# Pressure_Sensor.net
KiCad netlist of a schematic drawn in Altium Designer
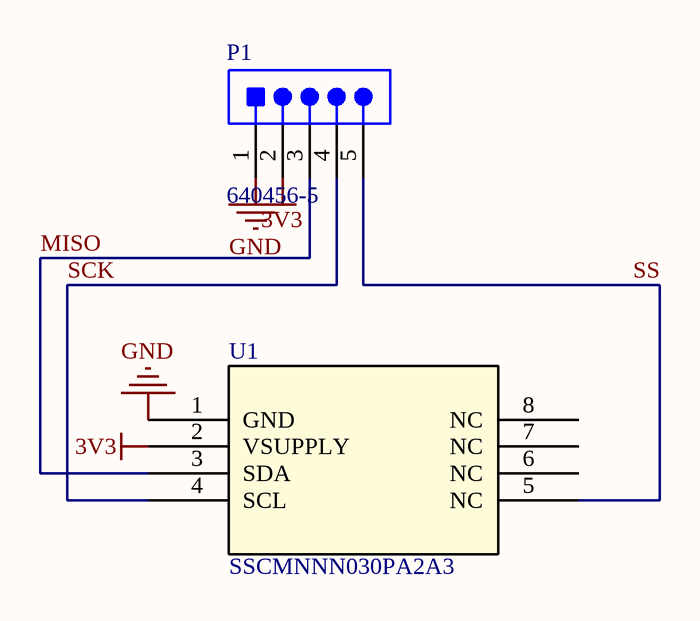
[diagram p0: Pressure Sensor.SchDoc]

(export (version "E")
  (design (tool "Eeschema 10.0.6"))
  (components
    (comp (ref "P1")
      (value "640456-5")
      (footprint "TECO-640456-5")
      (fields (field (name "MANUFACTURER") "TE Connectivity"))
      (libsource (lib "Altium Content Vault") (part "CN-1P-M-R5"))
    )
    (comp (ref "U1")
      (value "SSCMNNN030PA2A3")
      (footprint "SSCMNN_HNW-L")
      (description "No Description Available")
      (fields (field (name "COPYRIGHT") "Copyright (C) 2018 Accelerated Designs. All rights reserved"))
      (libsource (lib "2020-10-01_16-01-06") (part "SSCMNNN030PA2A3"))
    )
  )
  (nets
    (net (code "1") (name "/MISO") (class "Default")
      (node (ref "P1") (pin "3") (pinfunction "TXO_3") (pintype "passive"))
      (node (ref "U1") (pin "3") (pinfunction "SDA_3") (pintype "passive"))
    )
    (net (code "2") (name "/SCK") (class "Default")
      (node (ref "P1") (pin "4") (pinfunction "VCC_4") (pintype "passive"))
      (node (ref "U1") (pin "4") (pinfunction "SCL_4") (pintype "passive"))
    )
    (net (code "3") (name "/SS") (class "Default")
      (node (ref "P1") (pin "5") (pinfunction "CTS_5") (pintype "passive"))
      (node (ref "U1") (pin "5") (pinfunction "NC_5") (pintype "passive"))
    )
    (net (code "4") (name "3V3") (class "Default")
      (node (ref "P1") (pin "2") (pinfunction "RXI_2") (pintype "passive"))
      (node (ref "U1") (pin "2") (pinfunction "VSUPPLY_2") (pintype "power_in"))
    )
    (net (code "5") (name "GND") (class "Default")
      (node (ref "P1") (pin "1") (pinfunction "DTR_1") (pintype "passive"))
      (node (ref "U1") (pin "1") (pinfunction "GND_1") (pintype "passive"))
    )
    (net (code "6") (name "unconnected-(U1-NC-Pad6)") (class "Default")
      (node (ref "U1") (pin "6") (pinfunction "NC_6") (pintype "passive"))
    )
    (net (code "7") (name "unconnected-(U1-NC-Pad7)") (class "Default")
      (node (ref "U1") (pin "7") (pinfunction "NC_7") (pintype "passive"))
    )
    (net (code "8") (name "unconnected-(U1-NC-Pad8)") (class "Default")
      (node (ref "U1") (pin "8") (pinfunction "NC_8") (pintype "passive"))
    )
  )
)
